# 05_ESP32.net
KiCad netlist of a schematic drawn in Altium Designer
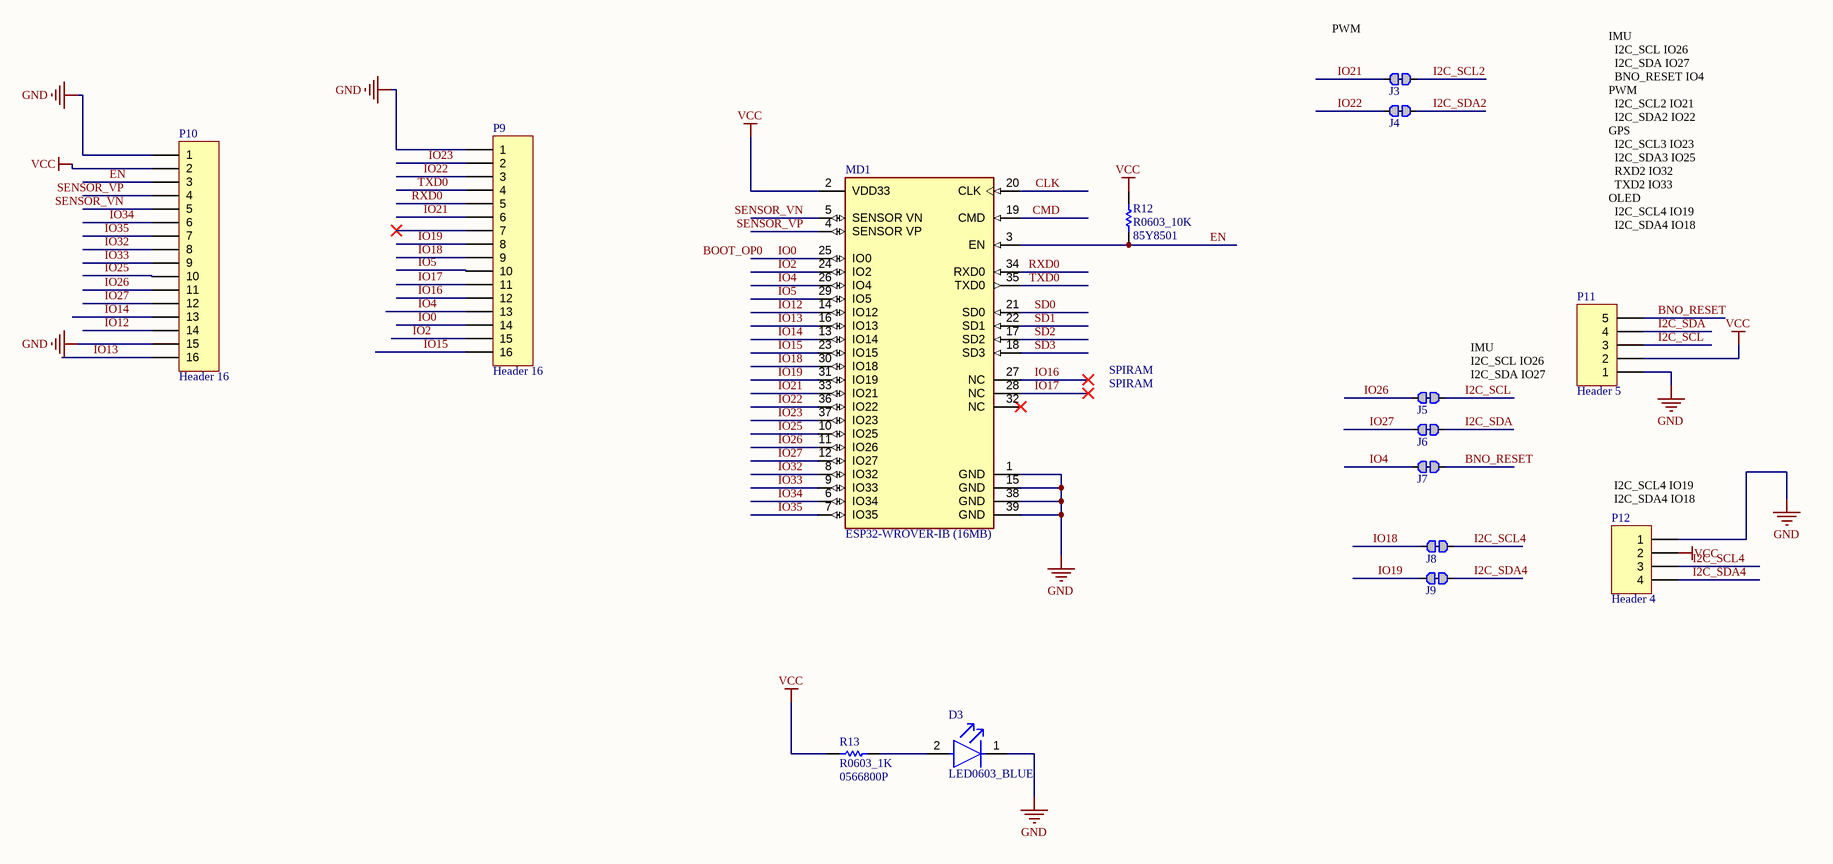
[diagram p0: 05_ESP32.SchDoc]

(export (version "E")
  (design (tool "Eeschema 10.0.6"))
  (components
    (comp (ref "D3")
      (value "LED0603_BLUE")
      (footprint "FP-LTST-C191TBKT-MFG")
      (description "LED BLUE CLEAR CHIP SMD")
      (libsource (lib "Altium Content Vault") (part "8706943c75ba83719d021d2fdc84c58"))
    )
    (comp (ref "J3")
      (value "Jumper")
      (footprint "0402-0R")
      (description "Resistor")
      (libsource (lib "RBS_library") (part "Jumper"))
    )
    (comp (ref "J4")
      (value "Jumper")
      (footprint "0402-0R")
      (description "Resistor")
      (libsource (lib "RBS_library") (part "Jumper"))
    )
    (comp (ref "J5")
      (value "Jumper")
      (footprint "0402-0R")
      (description "Resistor")
      (libsource (lib "RBS_library") (part "Jumper"))
    )
    (comp (ref "J6")
      (value "Jumper")
      (footprint "0402-0R")
      (description "Resistor")
      (libsource (lib "RBS_library") (part "Jumper"))
    )
    (comp (ref "J7")
      (value "Jumper")
      (footprint "0402-0R")
      (description "Resistor")
      (libsource (lib "RBS_library") (part "Jumper"))
    )
    (comp (ref "J8")
      (value "Jumper")
      (footprint "0402-0R")
      (description "Resistor")
      (libsource (lib "RBS_library") (part "Jumper"))
    )
    (comp (ref "J9")
      (value "Jumper")
      (footprint "0402-0R")
      (description "Resistor")
      (libsource (lib "RBS_library") (part "Jumper"))
    )
    (comp (ref "MD1")
      (value "ESP32-WROVER-IB (16MB)")
      (footprint "FP-ESP32-WROVER-MFG")
      (description "SMD MODULE, ESP32-D0WDQ6")
      (fields
        (field (name "OCTOPART") "https://octopart.com/esp32-wrover-espressif+systems-89171348")
        (field (name "MANUFACTURER") "Espressif Systems")
      )
      (libsource (lib "Altium Content Vault") (part "b149d9f4d1006c9afe7408d01ae8443"))
    )
    (comp (ref "P9")
      (value "Header 16")
      (footprint "HDR1X16")
      (description "Header, 16-Pin")
      (fields (field (name "PUBLISHER") "Altium Limited"))
      (libsource (lib "Miscellaneous Connectors") (part "Header 16"))
    )
    (comp (ref "P10")
      (value "Header 16")
      (footprint "HDR1X16")
      (description "Header, 16-Pin")
      (fields (field (name "PUBLISHER") "Altium Limited"))
      (libsource (lib "Miscellaneous Connectors") (part "Header 16"))
    )
    (comp (ref "P11")
      (value "Header 5")
      (footprint "HDR1X5")
      (description "Header, 5-Pin")
      (fields (field (name "PUBLISHER") "Altium Limited"))
      (libsource (lib "Miscellaneous Connectors") (part "Header 5"))
    )
    (comp (ref "P12")
      (value "Header 4")
      (footprint "HDR1X4")
      (description "Header, 4-Pin")
      (fields (field (name "PUBLISHER") "Altium Limited"))
      (libsource (lib "Miscellaneous Connectors") (part "Header 4"))
    )
    (comp (ref "R12")
      (value "R0603_10K")
      (footprint "RESC1609X55X30LL15T15")
      (description "PANASONIC - ERJ-3EKF1002V. - THICK FILM CHIP RES, 0603, 1%, PRECISION")
      (fields
        (field (name "SUPPLIER PART NUMBER 1") "85Y8501")
        (field (name "MANUFACTURER") "Panasonic")
        (field (name "MANUFACTURER PART NUMBER") "ERJ-3EKF1002V")
      )
      (libsource (lib "RBS_library") (part "R0603"))
    )
    (comp (ref "R13")
      (value "R0603_1K")
      (footprint "RESC1609X55X30LL15T15")
      (description "Res Thin Film 0603 1K Ohm 0.1% 1/10W ±25ppm/°C Molded SMD SMD Punched Carrier T/R")
      (fields
        (field (name "SUPPLIER PART NUMBER 1") "0566800P")
        (field (name "MANUFACTURER") "Panasonic")
        (field (name "MANUFACTURER PART NUMBER") "ERA-3AEB102V")
      )
      (libsource (lib "RBS_library") (part "R0603"))
    )
  )
  (nets
    (net (code "1") (name "/BNO_RESET") (class "Default")
      (node (ref "J7") (pin "2") (pinfunction "2_2") (pintype "passive"))
      (node (ref "P11") (pin "5") (pinfunction "5_5") (pintype "passive"))
    )
    (net (code "2") (name "/BOOT_OP0") (class "Default")
      (node (ref "MD1") (pin "25") (pinfunction "IO0_25") (pintype "bidirectional"))
      (node (ref "P9") (pin "14") (pinfunction "14_14") (pintype "passive"))
    )
    (net (code "3") (name "/CLK") (class "Default")
      (node (ref "MD1") (pin "20") (pinfunction "CLK_20") (pintype "input"))
    )
    (net (code "4") (name "/CMD") (class "Default")
      (node (ref "MD1") (pin "19") (pinfunction "CMD_19") (pintype "input"))
    )
    (net (code "5") (name "/EN") (class "Default")
      (node (ref "MD1") (pin "3") (pinfunction "EN_3") (pintype "input"))
      (node (ref "P10") (pin "3") (pinfunction "3_3") (pintype "passive"))
      (node (ref "R12") (pin "1") (pinfunction "1_1") (pintype "passive"))
    )
    (net (code "6") (name "/I2C_SCL") (class "Default")
      (node (ref "J5") (pin "2") (pinfunction "2_2") (pintype "passive"))
      (node (ref "P11") (pin "3") (pinfunction "3_3") (pintype "passive"))
    )
    (net (code "7") (name "/I2C_SCL2") (class "Default")
      (node (ref "J3") (pin "2") (pinfunction "2_2") (pintype "passive"))
    )
    (net (code "8") (name "/I2C_SCL4") (class "Default")
      (node (ref "J8") (pin "2") (pinfunction "2_2") (pintype "passive"))
      (node (ref "P12") (pin "3") (pinfunction "3_3") (pintype "passive"))
    )
    (net (code "9") (name "/I2C_SDA") (class "Default")
      (node (ref "J6") (pin "2") (pinfunction "2_2") (pintype "passive"))
      (node (ref "P11") (pin "4") (pinfunction "4_4") (pintype "passive"))
    )
    (net (code "10") (name "/I2C_SDA2") (class "Default")
      (node (ref "J4") (pin "2") (pinfunction "2_2") (pintype "passive"))
    )
    (net (code "11") (name "/I2C_SDA4") (class "Default")
      (node (ref "J9") (pin "2") (pinfunction "2_2") (pintype "passive"))
      (node (ref "P12") (pin "4") (pinfunction "4_4") (pintype "passive"))
    )
    (net (code "12") (name "/IO2") (class "Default")
      (node (ref "MD1") (pin "24") (pinfunction "IO2_24") (pintype "bidirectional"))
      (node (ref "P9") (pin "15") (pinfunction "15_15") (pintype "passive"))
    )
    (net (code "13") (name "/IO4") (class "Default")
      (node (ref "J7") (pin "1") (pinfunction "1_1") (pintype "passive"))
      (node (ref "MD1") (pin "26") (pinfunction "IO4_26") (pintype "bidirectional"))
      (node (ref "P9") (pin "13") (pinfunction "13_13") (pintype "passive"))
    )
    (net (code "14") (name "/IO5") (class "Default")
      (node (ref "MD1") (pin "29") (pinfunction "IO5_29") (pintype "bidirectional"))
      (node (ref "P9") (pin "10") (pinfunction "10_10") (pintype "passive"))
    )
    (net (code "15") (name "/IO12") (class "Default")
      (node (ref "MD1") (pin "14") (pinfunction "IO12_14") (pintype "bidirectional"))
      (node (ref "P10") (pin "14") (pinfunction "14_14") (pintype "passive"))
    )
    (net (code "16") (name "/IO13") (class "Default")
      (node (ref "MD1") (pin "16") (pinfunction "IO13_16") (pintype "bidirectional"))
      (node (ref "P10") (pin "16") (pinfunction "16_16") (pintype "passive"))
    )
    (net (code "17") (name "/IO14") (class "Default")
      (node (ref "MD1") (pin "13") (pinfunction "IO14_13") (pintype "bidirectional"))
      (node (ref "P10") (pin "13") (pinfunction "13_13") (pintype "passive"))
    )
    (net (code "18") (name "/IO15") (class "Default")
      (node (ref "MD1") (pin "23") (pinfunction "IO15_23") (pintype "bidirectional"))
      (node (ref "P9") (pin "16") (pinfunction "16_16") (pintype "passive"))
    )
    (net (code "19") (name "/IO16") (class "Default")
      (node (ref "MD1") (pin "27") (pinfunction "NC_27") (pintype "passive"))
      (node (ref "P9") (pin "12") (pinfunction "12_12") (pintype "passive"))
    )
    (net (code "20") (name "/IO17") (class "Default")
      (node (ref "MD1") (pin "28") (pinfunction "NC_28") (pintype "passive"))
      (node (ref "P9") (pin "11") (pinfunction "11_11") (pintype "passive"))
    )
    (net (code "21") (name "/IO18") (class "Default")
      (node (ref "J8") (pin "1") (pinfunction "1_1") (pintype "passive"))
      (node (ref "MD1") (pin "30") (pinfunction "IO18_30") (pintype "bidirectional"))
      (node (ref "P9") (pin "9") (pinfunction "9_9") (pintype "passive"))
    )
    (net (code "22") (name "/IO19") (class "Default")
      (node (ref "J9") (pin "1") (pinfunction "1_1") (pintype "passive"))
      (node (ref "MD1") (pin "31") (pinfunction "IO19_31") (pintype "bidirectional"))
      (node (ref "P9") (pin "8") (pinfunction "8_8") (pintype "passive"))
    )
    (net (code "23") (name "/IO21") (class "Default")
      (node (ref "J3") (pin "1") (pinfunction "1_1") (pintype "passive"))
      (node (ref "MD1") (pin "33") (pinfunction "IO21_33") (pintype "bidirectional"))
      (node (ref "P9") (pin "6") (pinfunction "6_6") (pintype "passive"))
    )
    (net (code "24") (name "/IO22") (class "Default")
      (node (ref "J4") (pin "1") (pinfunction "1_1") (pintype "passive"))
      (node (ref "MD1") (pin "36") (pinfunction "IO22_36") (pintype "bidirectional"))
      (node (ref "P9") (pin "3") (pinfunction "3_3") (pintype "passive"))
    )
    (net (code "25") (name "/IO23") (class "Default")
      (node (ref "MD1") (pin "37") (pinfunction "IO23_37") (pintype "bidirectional"))
      (node (ref "P9") (pin "2") (pinfunction "2_2") (pintype "passive"))
    )
    (net (code "26") (name "/IO25") (class "Default")
      (node (ref "MD1") (pin "10") (pinfunction "IO25_10") (pintype "bidirectional"))
      (node (ref "P10") (pin "10") (pinfunction "10_10") (pintype "passive"))
    )
    (net (code "27") (name "/IO26") (class "Default")
      (node (ref "J5") (pin "1") (pinfunction "1_1") (pintype "passive"))
      (node (ref "MD1") (pin "11") (pinfunction "IO26_11") (pintype "bidirectional"))
      (node (ref "P10") (pin "11") (pinfunction "11_11") (pintype "passive"))
    )
    (net (code "28") (name "/IO27") (class "Default")
      (node (ref "J6") (pin "1") (pinfunction "1_1") (pintype "passive"))
      (node (ref "MD1") (pin "12") (pinfunction "IO27_12") (pintype "bidirectional"))
      (node (ref "P10") (pin "12") (pinfunction "12_12") (pintype "passive"))
    )
    (net (code "29") (name "/IO32") (class "Default")
      (node (ref "MD1") (pin "8") (pinfunction "IO32_8") (pintype "bidirectional"))
      (node (ref "P10") (pin "8") (pinfunction "8_8") (pintype "passive"))
    )
    (net (code "30") (name "/IO33") (class "Default")
      (node (ref "MD1") (pin "9") (pinfunction "IO33_9") (pintype "bidirectional"))
      (node (ref "P10") (pin "9") (pinfunction "9_9") (pintype "passive"))
    )
    (net (code "31") (name "/IO34") (class "Default")
      (node (ref "MD1") (pin "6") (pinfunction "IO34_6") (pintype "bidirectional"))
      (node (ref "P10") (pin "6") (pinfunction "6_6") (pintype "passive"))
    )
    (net (code "32") (name "/IO35") (class "Default")
      (node (ref "MD1") (pin "7") (pinfunction "IO35_7") (pintype "bidirectional"))
      (node (ref "P10") (pin "7") (pinfunction "7_7") (pintype "passive"))
    )
    (net (code "33") (name "/RXD0") (class "Default")
      (node (ref "MD1") (pin "34") (pinfunction "RXD0_34") (pintype "input"))
      (node (ref "P9") (pin "5") (pinfunction "5_5") (pintype "passive"))
    )
    (net (code "34") (name "/SD0") (class "Default")
      (node (ref "MD1") (pin "21") (pinfunction "SD0_21") (pintype "input"))
    )
    (net (code "35") (name "/SD1") (class "Default")
      (node (ref "MD1") (pin "22") (pinfunction "SD1_22") (pintype "input"))
    )
    (net (code "36") (name "/SD2") (class "Default")
      (node (ref "MD1") (pin "17") (pinfunction "SD2_17") (pintype "input"))
    )
    (net (code "37") (name "/SD3") (class "Default")
      (node (ref "MD1") (pin "18") (pinfunction "SD3_18") (pintype "input"))
    )
    (net (code "38") (name "/SENSOR_VN") (class "Default")
      (node (ref "MD1") (pin "5") (pinfunction "SENSOR_VN_5") (pintype "bidirectional"))
      (node (ref "P10") (pin "5") (pinfunction "5_5") (pintype "passive"))
    )
    (net (code "39") (name "/SENSOR_VP") (class "Default")
      (node (ref "MD1") (pin "4") (pinfunction "SENSOR_VP_4") (pintype "bidirectional"))
      (node (ref "P10") (pin "4") (pinfunction "4_4") (pintype "passive"))
    )
    (net (code "40") (name "/TXD0") (class "Default")
      (node (ref "MD1") (pin "35") (pinfunction "TXD0_35") (pintype "output"))
      (node (ref "P9") (pin "4") (pinfunction "4_4") (pintype "passive"))
    )
    (net (code "41") (name "GND") (class "Default")
      (node (ref "D3") (pin "1") (pinfunction "C_1") (pintype "passive"))
      (node (ref "MD1") (pin "1") (pinfunction "GND_1") (pintype "power_in"))
      (node (ref "MD1") (pin "15") (pinfunction "GND_15") (pintype "power_in"))
      (node (ref "MD1") (pin "38") (pinfunction "GND_38") (pintype "power_in"))
      (node (ref "MD1") (pin "39") (pinfunction "GND_39") (pintype "power_in"))
      (node (ref "P10") (pin "1") (pinfunction "1_1") (pintype "passive"))
      (node (ref "P10") (pin "15") (pinfunction "15_15") (pintype "passive"))
      (node (ref "P11") (pin "1") (pinfunction "1_1") (pintype "passive"))
      (node (ref "P12") (pin "1") (pinfunction "1_1") (pintype "passive"))
      (node (ref "P9") (pin "1") (pinfunction "1_1") (pintype "passive"))
    )
    (net (code "42") (name "Net-(D3-A)") (class "Default")
      (node (ref "D3") (pin "2") (pinfunction "A_2") (pintype "passive"))
      (node (ref "R13") (pin "1") (pinfunction "1_1") (pintype "passive"))
    )
    (net (code "43") (name "VCC") (class "Default")
      (node (ref "MD1") (pin "2") (pinfunction "VDD33_2") (pintype "power_in"))
      (node (ref "P10") (pin "2") (pinfunction "2_2") (pintype "passive"))
      (node (ref "P11") (pin "2") (pinfunction "2_2") (pintype "passive"))
      (node (ref "P12") (pin "2") (pinfunction "2_2") (pintype "passive"))
      (node (ref "R12") (pin "2") (pinfunction "2_2") (pintype "passive"))
      (node (ref "R13") (pin "2") (pinfunction "2_2") (pintype "passive"))
    )
    (net (code "44") (name "unconnected-(MD1-NC-Pad32)") (class "Default")
      (node (ref "MD1") (pin "32") (pinfunction "NC_32") (pintype "passive+no_connect"))
    )
    (net (code "45") (name "unconnected-(P9-Pad7)") (class "Default")
      (node (ref "P9") (pin "7") (pinfunction "7_7") (pintype "passive+no_connect"))
    )
  )
)
